# baseband_amp.net
KiCad netlist of a schematic drawn in EAGLE
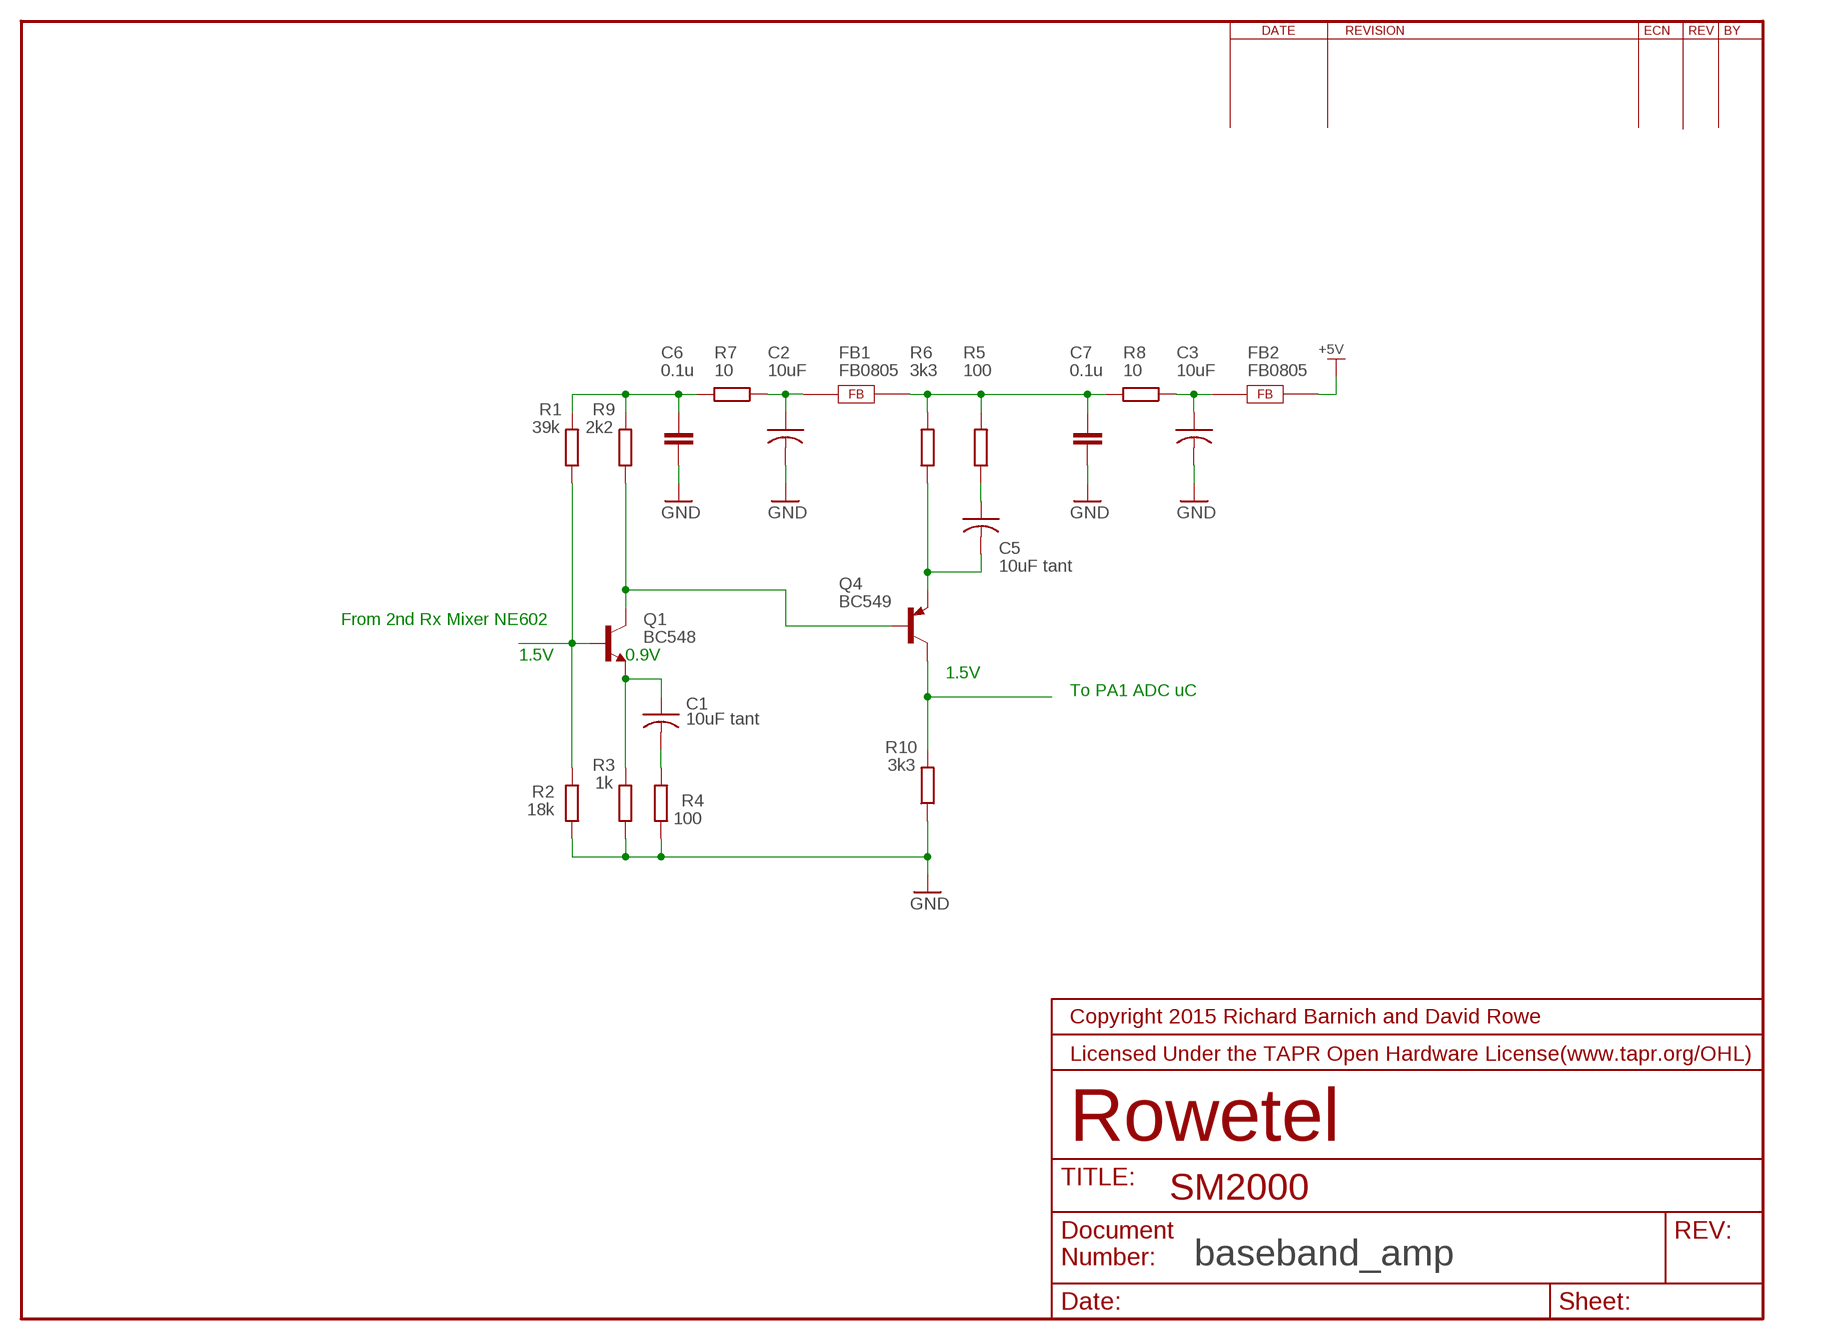
[diagram p0: schematic, sheet 1]

(export (version "E")
  (design (tool "Eeschema 10.0.6"))
  (components
    (comp (ref "C1")
      (value "10uF tant")
      (footprint "eagle-import:C1210")
      (libsource (lib "eagle-import") (part "CAP-1210"))
    )
    (comp (ref "C2")
      (value "10uF")
      (footprint "eagle-import:C1210")
      (libsource (lib "eagle-import") (part "CAP-1210"))
    )
    (comp (ref "C3")
      (value "10uF")
      (footprint "eagle-import:C1210")
      (libsource (lib "eagle-import") (part "CAP-1210"))
    )
    (comp (ref "C5")
      (value "10uF tant")
      (footprint "eagle-import:C1210")
      (libsource (lib "eagle-import") (part "CAP-1210"))
    )
    (comp (ref "C6")
      (value "0.1u")
      (footprint "eagle-import:C025-024X044")
      (libsource (lib "eagle-import") (part "C-EU025-024X044"))
    )
    (comp (ref "C7")
      (value "0.1u")
      (footprint "eagle-import:C025-024X044")
      (libsource (lib "eagle-import") (part "C-EU025-024X044"))
    )
    (comp (ref "FB1")
      (value "FB0805")
      (footprint "eagle-import:FE0805")
      (libsource (lib "eagle-import") (part "FB0805"))
    )
    (comp (ref "FB2")
      (value "FB0805")
      (footprint "eagle-import:FE0805")
      (libsource (lib "eagle-import") (part "FB0805"))
    )
    (comp (ref "Q1")
      (value "BC548")
      (footprint "eagle-import:SOT23-EBC")
      (libsource (lib "eagle-import") (part "-NPN-SOT23-EBC"))
    )
    (comp (ref "Q4")
      (value "BC549")
      (footprint "eagle-import:TO5")
      (libsource (lib "eagle-import") (part "2N2905"))
    )
    (comp (ref "R1")
      (value "39k")
      (footprint "eagle-import:RESC2012X70N")
      (libsource (lib "eagle-import") (part "RESISTOR_0805"))
    )
    (comp (ref "R2")
      (value "18k")
      (footprint "eagle-import:RESC2012X70N")
      (libsource (lib "eagle-import") (part "RESISTOR_0805"))
    )
    (comp (ref "R3")
      (value "1k")
      (footprint "eagle-import:RESC2012X70N")
      (libsource (lib "eagle-import") (part "RESISTOR_0805"))
    )
    (comp (ref "R4")
      (value "100")
      (footprint "eagle-import:RESC2012X70N")
      (libsource (lib "eagle-import") (part "RESISTOR_0805"))
    )
    (comp (ref "R5")
      (value "100")
      (footprint "eagle-import:RESC2012X70N")
      (libsource (lib "eagle-import") (part "RESISTOR_0805"))
    )
    (comp (ref "R6")
      (value "3k3")
      (footprint "eagle-import:RESC2012X70N")
      (libsource (lib "eagle-import") (part "RESISTOR_0805"))
    )
    (comp (ref "R7")
      (value "10")
      (footprint "eagle-import:RESC2012X70N")
      (libsource (lib "eagle-import") (part "RESISTOR_0805"))
    )
    (comp (ref "R8")
      (value "10")
      (footprint "eagle-import:RESC2012X70N")
      (libsource (lib "eagle-import") (part "RESISTOR_0805"))
    )
    (comp (ref "R9")
      (value "2k2")
      (footprint "eagle-import:RESC2012X70N")
      (libsource (lib "eagle-import") (part "RESISTOR_0805"))
    )
    (comp (ref "R10")
      (value "3k3")
      (footprint "eagle-import:RESC2012X70N")
      (libsource (lib "eagle-import") (part "RESISTOR_0805"))
    )
  )
  (nets
    (net (code "1") (name "+5V") (class "Default")
      (node (ref "FB2") (pin "2") (pinfunction "2_2") (pintype "passive"))
    )
    (net (code "2") (name "GND") (class "Default")
      (node (ref "C2") (pin "2") (pinfunction "2_2") (pintype "passive"))
      (node (ref "C3") (pin "2") (pinfunction "2_2") (pintype "passive"))
      (node (ref "C6") (pin "2") (pinfunction "2_2") (pintype "passive"))
      (node (ref "C7") (pin "2") (pinfunction "2_2") (pintype "passive"))
      (node (ref "R10") (pin "1") (pinfunction "1_1") (pintype "passive"))
      (node (ref "R2") (pin "1") (pinfunction "1_1") (pintype "passive"))
      (node (ref "R3") (pin "1") (pinfunction "1_1") (pintype "passive"))
      (node (ref "R4") (pin "1") (pinfunction "1_1") (pintype "passive"))
    )
    (net (code "3") (name "Net-(C1-Pad1)") (class "Default")
      (node (ref "C1") (pin "1") (pinfunction "1_1") (pintype "passive"))
      (node (ref "Q1") (pin "E") (pinfunction "E_E") (pintype "passive"))
      (node (ref "R3") (pin "2") (pinfunction "2_2") (pintype "passive"))
    )
    (net (code "4") (name "Net-(C1-Pad2)") (class "Default")
      (node (ref "C1") (pin "2") (pinfunction "2_2") (pintype "passive"))
      (node (ref "R4") (pin "2") (pinfunction "2_2") (pintype "passive"))
    )
    (net (code "5") (name "Net-(C2-Pad1)") (class "Default")
      (node (ref "C2") (pin "1") (pinfunction "1_1") (pintype "passive"))
      (node (ref "FB1") (pin "1") (pinfunction "1_1") (pintype "passive"))
      (node (ref "R7") (pin "1") (pinfunction "1_1") (pintype "passive"))
    )
    (net (code "6") (name "Net-(C3-Pad1)") (class "Default")
      (node (ref "C3") (pin "1") (pinfunction "1_1") (pintype "passive"))
      (node (ref "FB2") (pin "1") (pinfunction "1_1") (pintype "passive"))
      (node (ref "R8") (pin "1") (pinfunction "1_1") (pintype "passive"))
    )
    (net (code "7") (name "Net-(C5-Pad1)") (class "Default")
      (node (ref "C5") (pin "1") (pinfunction "1_1") (pintype "passive"))
      (node (ref "R5") (pin "1") (pinfunction "1_1") (pintype "passive"))
    )
    (net (code "8") (name "Net-(C6-Pad1)") (class "Default")
      (node (ref "C6") (pin "1") (pinfunction "1_1") (pintype "passive"))
      (node (ref "R1") (pin "2") (pinfunction "2_2") (pintype "passive"))
      (node (ref "R7") (pin "2") (pinfunction "2_2") (pintype "passive"))
      (node (ref "R9") (pin "2") (pinfunction "2_2") (pintype "passive"))
    )
    (net (code "9") (name "Net-(C7-Pad1)") (class "Default")
      (node (ref "C7") (pin "1") (pinfunction "1_1") (pintype "passive"))
      (node (ref "FB1") (pin "2") (pinfunction "2_2") (pintype "passive"))
      (node (ref "R5") (pin "2") (pinfunction "2_2") (pintype "passive"))
      (node (ref "R6") (pin "2") (pinfunction "2_2") (pintype "passive"))
      (node (ref "R8") (pin "2") (pinfunction "2_2") (pintype "passive"))
    )
    (net (code "10") (name "Net-(Q1-PadB)") (class "Default")
      (node (ref "Q1") (pin "B") (pinfunction "B_B") (pintype "passive"))
      (node (ref "R1") (pin "1") (pinfunction "1_1") (pintype "passive"))
      (node (ref "R2") (pin "2") (pinfunction "2_2") (pintype "passive"))
    )
    (net (code "11") (name "Net-(Q4-B)") (class "Default")
      (node (ref "Q1") (pin "C") (pinfunction "C_C") (pintype "passive"))
      (node (ref "Q4") (pin "2") (pinfunction "B_2") (pintype "passive"))
      (node (ref "R9") (pin "1") (pinfunction "1_1") (pintype "passive"))
    )
    (net (code "12") (name "Net-(Q4-C)") (class "Default")
      (node (ref "Q4") (pin "3") (pinfunction "C_3") (pintype "passive"))
      (node (ref "R10") (pin "2") (pinfunction "2_2") (pintype "passive"))
    )
    (net (code "13") (name "Net-(Q4-E)") (class "Default")
      (node (ref "C5") (pin "2") (pinfunction "2_2") (pintype "passive"))
      (node (ref "Q4") (pin "1") (pinfunction "E_1") (pintype "passive"))
      (node (ref "R6") (pin "1") (pinfunction "1_1") (pintype "passive"))
    )
  )
)
